# button_bit.net
KiCad netlist of a schematic drawn in EAGLE
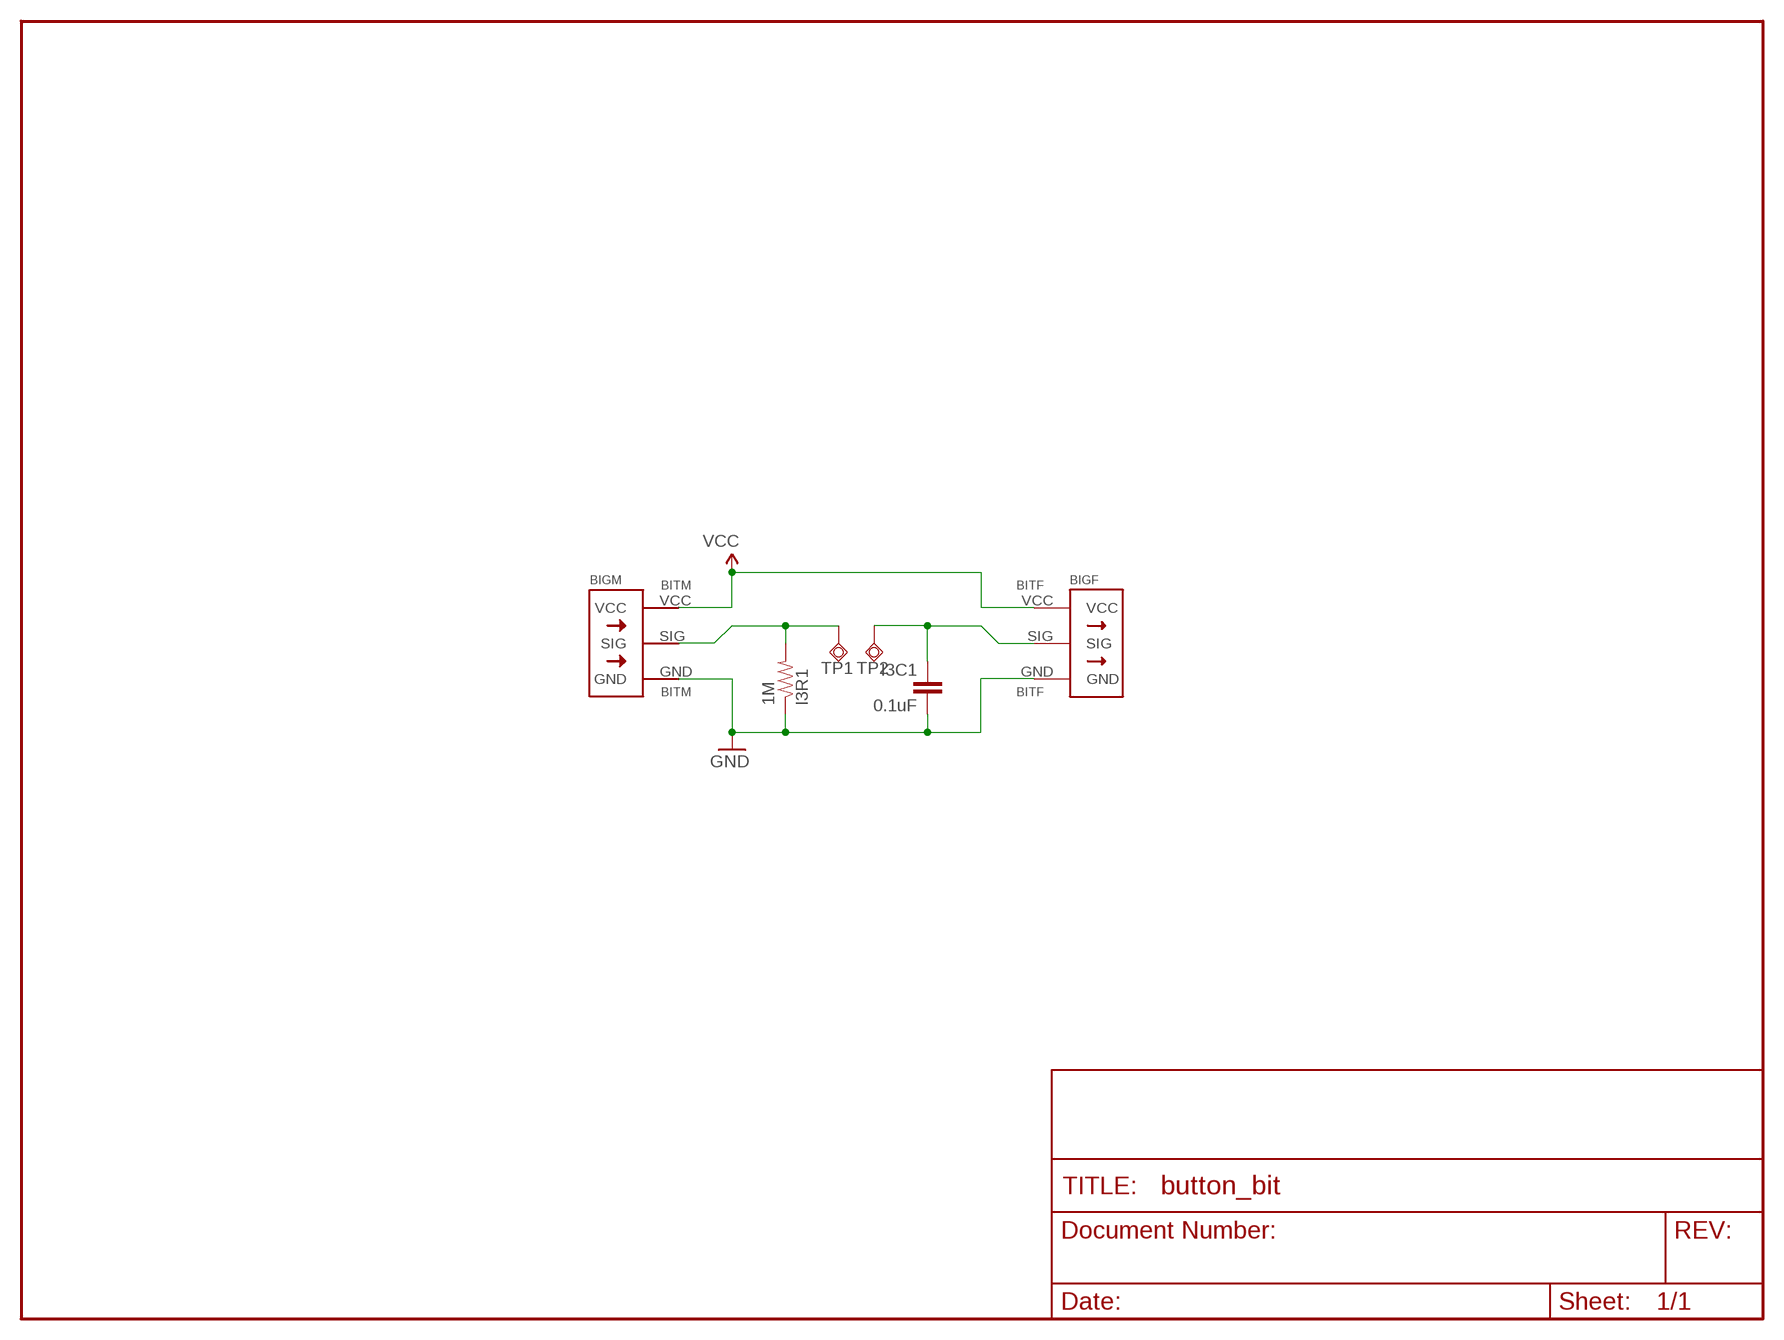
[diagram p0: schematic, sheet 1]

(export (version "E")
  (design (tool "Eeschema 10.0.6"))
  (components
    (comp (ref "BITF")
      (value "BITF")
      (footprint "eagle-import:BITM")
      (libsource (lib "eagle-import") (part "BITF"))
    )
    (comp (ref "BITM")
      (value "BITM")
      (footprint "eagle-import:BITM")
      (libsource (lib "eagle-import") (part "BITM"))
    )
    (comp (ref "I3C1")
      (value "0.1uF")
      (footprint "eagle-import:1206")
      (libsource (lib "eagle-import") (part "CAP1206"))
    )
    (comp (ref "I3R1")
      (value "1M")
      (footprint "eagle-import:0603-RES")
      (libsource (lib "eagle-import") (part "RESISTOR0603-RES"))
    )
    (comp (ref "TP1")
      (value "TPSQTP20SQ")
      (footprint "eagle-import:TP20SQ")
      (libsource (lib "eagle-import") (part "TPSQTP20SQ"))
    )
    (comp (ref "TP2")
      (value "TPSQTP20SQ")
      (footprint "eagle-import:TP20SQ")
      (libsource (lib "eagle-import") (part "TPSQTP20SQ"))
    )
  )
  (nets
    (net (code "1") (name "GND") (class "Default")
      (node (ref "BITF") (pin "GND") (pinfunction "GND_GND") (pintype "bidirectional"))
      (node (ref "BITM") (pin "GND") (pinfunction "GND_GND") (pintype "bidirectional"))
      (node (ref "I3C1") (pin "2") (pinfunction "2_2") (pintype "passive"))
      (node (ref "I3R1") (pin "1") (pinfunction "1_1") (pintype "passive"))
    )
    (net (code "2") (name "Net-(BITF-PadSIG)") (class "Default")
      (node (ref "BITF") (pin "SIG") (pinfunction "SIG_SIG") (pintype "bidirectional"))
      (node (ref "I3C1") (pin "1") (pinfunction "1_1") (pintype "passive"))
      (node (ref "TP2") (pin "TP") (pinfunction "TP_TP") (pintype "input"))
    )
    (net (code "3") (name "Net-(BITM-PadSIG)") (class "Default")
      (node (ref "BITM") (pin "SIG") (pinfunction "SIG_SIG") (pintype "bidirectional"))
      (node (ref "I3R1") (pin "2") (pinfunction "2_2") (pintype "passive"))
      (node (ref "TP1") (pin "TP") (pinfunction "TP_TP") (pintype "input"))
    )
    (net (code "4") (name "VCC") (class "Default")
      (node (ref "BITF") (pin "VCC") (pinfunction "VCC_VCC") (pintype "bidirectional"))
      (node (ref "BITM") (pin "VCC") (pinfunction "VCC_VCC") (pintype "bidirectional"))
    )
  )
)
